# MaTouch_Devkit_AC_Dimmer_V1_2.net
KiCad netlist of a schematic drawn in EAGLE
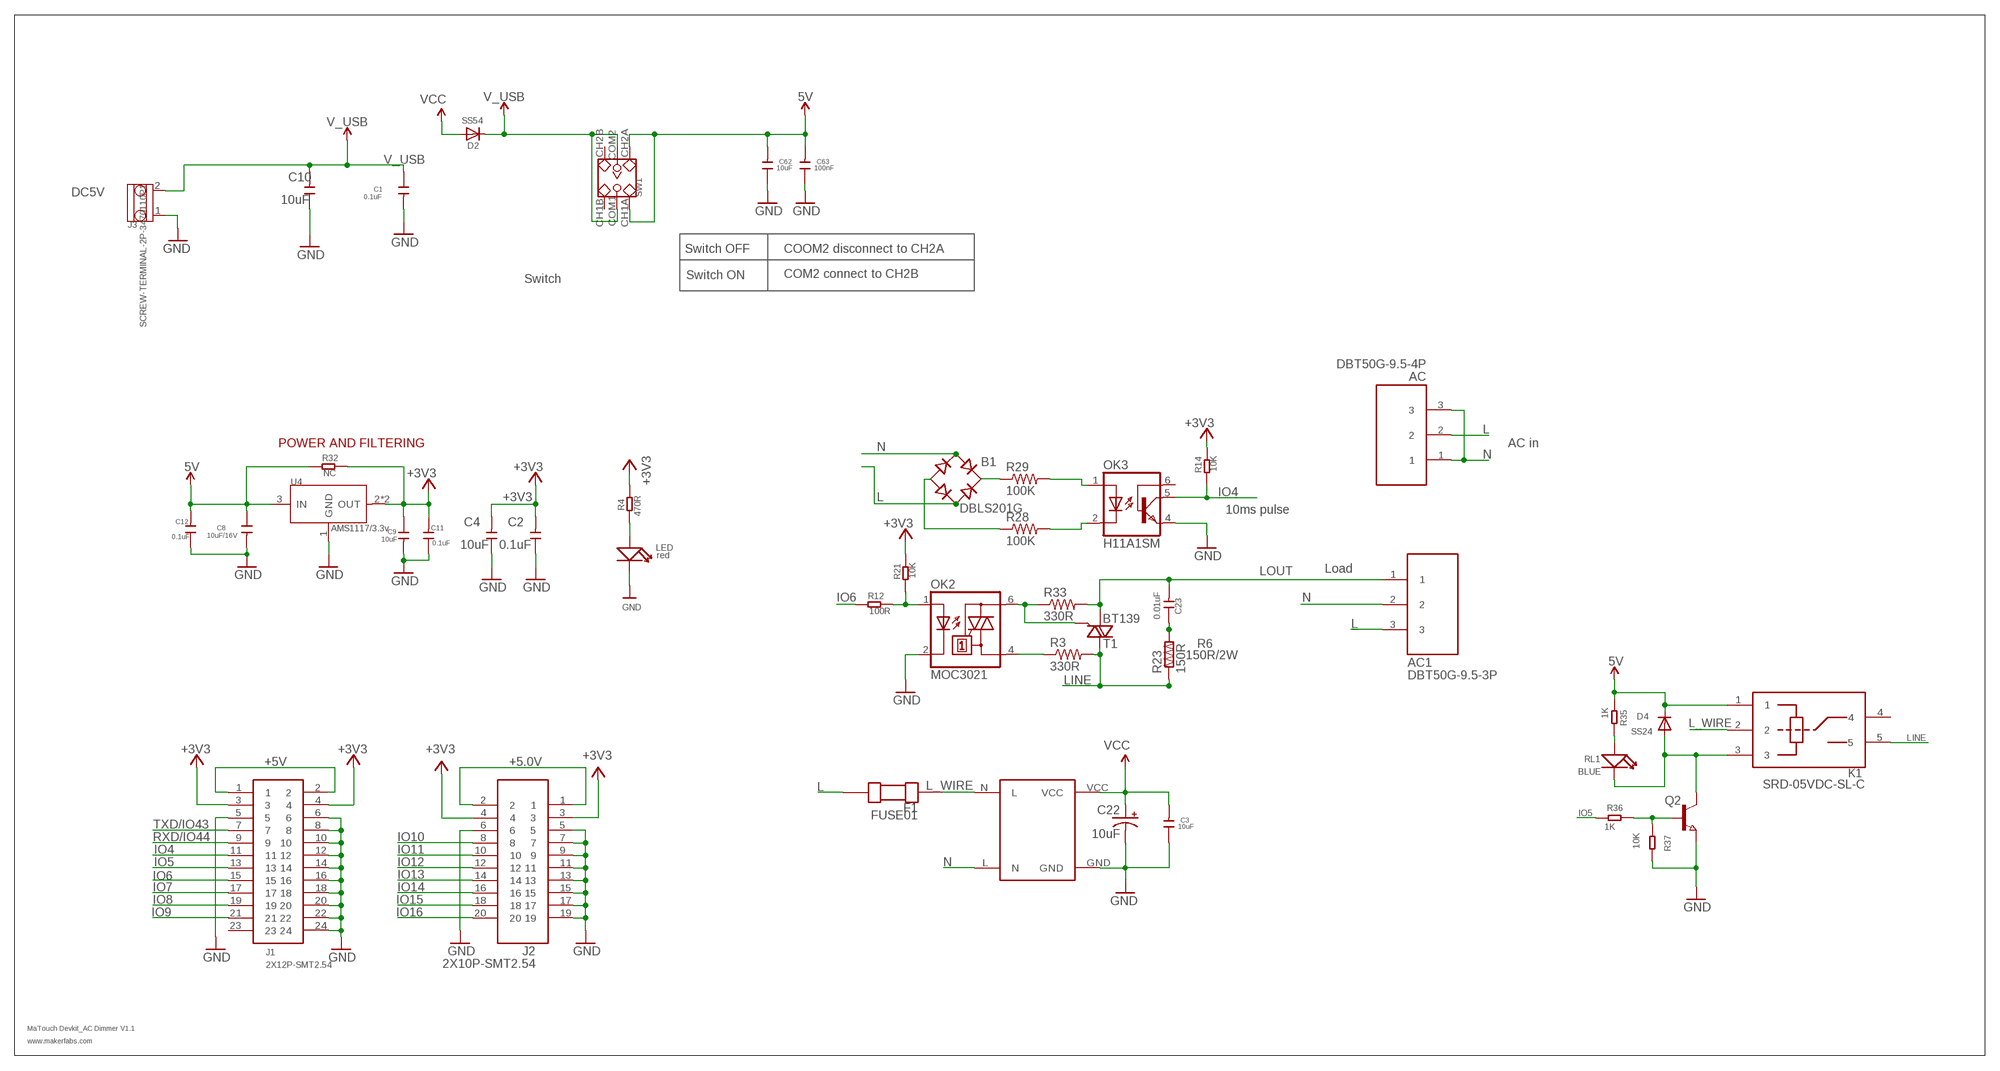
[diagram p0: schematic, sheet 1]

(export (version "E")
  (design (tool "Eeschema 10.0.6"))
  (components
    (comp (ref "AC")
      (value "DBT50G-9.5-4P")
      (footprint "eagle-import:THROUGH-HOLE-9.5")
      (libsource (lib "eagle-import") (part "DBT50G-9.5-3P"))
    )
    (comp (ref "AC1")
      (value "DBT50G-9.5-3P")
      (footprint "eagle-import:THROUGH-HOLE-9.5")
      (libsource (lib "eagle-import") (part "DBT50G-9.5-3P"))
    )
    (comp (ref "B1")
      (value "DBLS201G")
      (footprint "eagle-import:DBS")
      (libsource (lib "eagle-import") (part "DB?GLS201"))
    )
    (comp (ref "C1")
      (value "0.1uF")
      (footprint "eagle-import:0603")
      (libsource (lib "eagle-import") (part "C-0603"))
    )
    (comp (ref "C2")
      (value "0.1uF")
      (footprint "eagle-import:0603")
      (libsource (lib "eagle-import") (part "C-0603"))
    )
    (comp (ref "C3")
      (value "10uF")
      (footprint "eagle-import:0603")
      (libsource (lib "eagle-import") (part "C-0603"))
    )
    (comp (ref "C4")
      (value "10uF")
      (footprint "eagle-import:0603")
      (libsource (lib "eagle-import") (part "C-0603"))
    )
    (comp (ref "C8")
      (value "10uF/16V")
      (footprint "eagle-import:0603")
      (libsource (lib "eagle-import") (part "C-0603"))
    )
    (comp (ref "C9")
      (value "10uF")
      (footprint "eagle-import:0603")
      (libsource (lib "eagle-import") (part "C-0603"))
    )
    (comp (ref "C10")
      (value "10uF")
      (footprint "eagle-import:0603")
      (libsource (lib "eagle-import") (part "C-0603"))
    )
    (comp (ref "C11")
      (value "0.1uF")
      (footprint "eagle-import:0603")
      (libsource (lib "eagle-import") (part "C-0603"))
    )
    (comp (ref "C12")
      (value "0.1uF")
      (footprint "eagle-import:0603")
      (libsource (lib "eagle-import") (part "C-0603"))
    )
    (comp (ref "C22")
      (value "10uF")
      (footprint "eagle-import:EIA3528-KIT")
      (libsource (lib "eagle-import") (part "CAP_POL3528-KIT"))
    )
    (comp (ref "C23")
      (value "0.01uF")
      (footprint "eagle-import:DISCRETE_C0512_10.18")
      (libsource (lib "eagle-import") (part "DISCRETE_C-0512"))
    )
    (comp (ref "C62")
      (value "10uF")
      (footprint "eagle-import:0603")
      (libsource (lib "eagle-import") (part "C-0603"))
    )
    (comp (ref "C63")
      (value "100nF")
      (footprint "eagle-import:0603")
      (libsource (lib "eagle-import") (part "C-0603"))
    )
    (comp (ref "D2")
      (value "SS54")
      (footprint "eagle-import:SMADIODE")
      (libsource (lib "eagle-import") (part "DIODESMA"))
    )
    (comp (ref "D4")
      (value "SS24")
      (footprint "eagle-import:SMADIODE")
      (libsource (lib "eagle-import") (part "DIODESMA"))
    )
    (comp (ref "F1")
      (value "FUSE01")
      (footprint "eagle-import:FUSE01")
      (libsource (lib "eagle-import") (part "FUSE01"))
    )
    (comp (ref "J1")
      (value "2X12P-SMT2.54")
      (footprint "eagle-import:2X12P-SMT2.54")
      (libsource (lib "eagle-import") (part "2X12P-SMT2.54"))
    )
    (comp (ref "J2")
      (value "2X10P-SMT2.54")
      (footprint "eagle-import:2X10P-SMT2.54")
      (libsource (lib "eagle-import") (part "2X10P-SMT2.54"))
    )
    (comp (ref "J3")
      (value "SCREW-TERMINAL-2P-3470110P1")
      (footprint "eagle-import:2P-5.0")
      (libsource (lib "eagle-import") (part "SCREW-TERMINAL-2P-3470110P1"))
    )
    (comp (ref "K1")
      (value "JQC3FF")
      (footprint "eagle-import:DIP5_JQC3FF")
      (libsource (lib "eagle-import") (part "JQC3FF"))
    )
    (comp (ref "LED")
      (value "red")
      (footprint "eagle-import:DISCRETE_LED-0603")
      (libsource (lib "eagle-import") (part "DISCRETE_LED0603"))
    )
    (comp (ref "OK2")
      (value "MOC3021")
      (footprint "eagle-import:DIL6-SMD")
      (fields (field (name "MF") "FAIRCHILD SEMICONDUCTOR") (field (name "MPN") "MOC3031SM"))
      (libsource (lib "eagle-import") (part "MOC30S31"))
    )
    (comp (ref "OK3")
      (value "H11A1SM")
      (footprint "eagle-import:DIL6-SMD")
      (libsource (lib "eagle-import") (part "H11A?MS1"))
    )
    (comp (ref "Q2")
      (value "NPN-TRANSISTOR_SOT23")
      (footprint "eagle-import:SOT23")
      (libsource (lib "eagle-import") (part "NPN-TRANSISTOR_SOT23"))
    )
    (comp (ref "R3")
      (value "330R")
      (footprint "eagle-import:1206")
      (fields (field (name "K") "45K"))
      (libsource (lib "eagle-import") (part "RESISTOR1206"))
    )
    (comp (ref "R4")
      (value "470R")
      (footprint "eagle-import:R0603")
      (libsource (lib "eagle-import") (part "R-0603"))
    )
    (comp (ref "R6")
      (value "150R/2W")
      (footprint "eagle-import:R-0617")
      (libsource (lib "eagle-import") (part "R-0617"))
    )
    (comp (ref "R12")
      (value "100R")
      (footprint "eagle-import:R0603")
      (libsource (lib "eagle-import") (part "R-0603"))
    )
    (comp (ref "R14")
      (value "10K")
      (footprint "eagle-import:R0603")
      (libsource (lib "eagle-import") (part "R-0603"))
    )
    (comp (ref "R21")
      (value "10K")
      (footprint "eagle-import:R0603")
      (libsource (lib "eagle-import") (part "R-0603"))
    )
    (comp (ref "R23")
      (value "150R")
      (footprint "eagle-import:V234_12")
      (libsource (lib "eagle-import") (part "R-US_V234/12"))
    )
    (comp (ref "R28")
      (value "100K")
      (footprint "eagle-import:1206")
      (fields (field (name "K") "45K"))
      (libsource (lib "eagle-import") (part "RESISTOR1206"))
    )
    (comp (ref "R29")
      (value "100K")
      (footprint "eagle-import:1206")
      (fields (field (name "K") "45K"))
      (libsource (lib "eagle-import") (part "RESISTOR1206"))
    )
    (comp (ref "R32")
      (value "NC")
      (footprint "eagle-import:R0603")
      (libsource (lib "eagle-import") (part "R-0603"))
    )
    (comp (ref "R33")
      (value "330R")
      (footprint "eagle-import:1206")
      (fields (field (name "K") "45K"))
      (libsource (lib "eagle-import") (part "RESISTOR1206"))
    )
    (comp (ref "R35")
      (value "1K")
      (footprint "eagle-import:R0603")
      (libsource (lib "eagle-import") (part "R-0603"))
    )
    (comp (ref "R36")
      (value "1K")
      (footprint "eagle-import:R0603")
      (libsource (lib "eagle-import") (part "R-0603"))
    )
    (comp (ref "R37")
      (value "10K")
      (footprint "eagle-import:R0603")
      (libsource (lib "eagle-import") (part "R-0603"))
    )
    (comp (ref "RL1")
      (value "BLUE")
      (footprint "eagle-import:LED-0603")
      (libsource (lib "eagle-import") (part "LED'0603'"))
    )
    (comp (ref "SW1")
      (value "SWITCH-2CH-6P'90D'")
      (footprint "eagle-import:6P-2CH-2.54-9.0X3.6-90D")
      (libsource (lib "eagle-import") (part "SWITCH-2CH-6P'90D'"))
    )
    (comp (ref "T1")
      (value "BT139")
      (footprint "eagle-import:TO220AB")
      (libsource (lib "eagle-import") (part "BT136"))
    )
    (comp (ref "U4")
      (value "AMS1117/3.3v")
      (footprint "eagle-import:SOT89")
      (libsource (lib "eagle-import") (part "LD1117'SOT89'"))
    )
    (comp (ref "U5")
      (value "AC-DCHLK01")
      (footprint "eagle-import:HLK-PM01")
      (libsource (lib "eagle-import") (part "AC-DCHLK01"))
    )
  )
  (nets
    (net (code "1") (name "+3V3") (class "Default")
      (node (ref "C11") (pin "2") (pinfunction "2_2") (pintype "passive"))
      (node (ref "C2") (pin "2") (pinfunction "2_2") (pintype "passive"))
      (node (ref "C4") (pin "2") (pinfunction "2_2") (pintype "passive"))
      (node (ref "C9") (pin "1") (pinfunction "1_1") (pintype "passive"))
      (node (ref "J1") (pin "3") (pinfunction "3_3") (pintype "bidirectional"))
      (node (ref "J1") (pin "4") (pinfunction "4_4") (pintype "bidirectional"))
      (node (ref "J2") (pin "3") (pinfunction "3_3") (pintype "bidirectional"))
      (node (ref "J2") (pin "4") (pinfunction "4_4") (pintype "bidirectional"))
      (node (ref "R14") (pin "2") (pinfunction "2_2") (pintype "passive"))
      (node (ref "R21") (pin "2") (pinfunction "2_2") (pintype "passive"))
      (node (ref "R32") (pin "2") (pinfunction "2_2") (pintype "passive"))
      (node (ref "R4") (pin "2") (pinfunction "2_2") (pintype "passive"))
      (node (ref "U4") (pin "2") (pinfunction "OUT_2") (pintype "bidirectional"))
      (node (ref "U4") (pin "4") (pinfunction "OUT_4") (pintype "bidirectional"))
    )
    (net (code "2") (name "/+5.0V") (class "Default")
      (node (ref "J2") (pin "1") (pinfunction "1_1") (pintype "bidirectional"))
      (node (ref "J2") (pin "2") (pinfunction "2_2") (pintype "bidirectional"))
    )
    (net (code "3") (name "/+5V") (class "Default")
      (node (ref "J1") (pin "1") (pinfunction "1_1") (pintype "bidirectional"))
      (node (ref "J1") (pin "2") (pinfunction "2_2") (pintype "bidirectional"))
    )
    (net (code "4") (name "/IO4") (class "Default")
      (node (ref "J1") (pin "11") (pinfunction "11_11") (pintype "bidirectional"))
      (node (ref "OK3") (pin "5") (pinfunction "COL_5") (pintype "passive"))
      (node (ref "R14") (pin "1") (pinfunction "1_1") (pintype "passive"))
    )
    (net (code "5") (name "/IO5") (class "Default")
      (node (ref "J1") (pin "13") (pinfunction "13_13") (pintype "bidirectional"))
      (node (ref "R36") (pin "1") (pinfunction "1_1") (pintype "passive"))
    )
    (net (code "6") (name "/IO6") (class "Default")
      (node (ref "J1") (pin "15") (pinfunction "15_15") (pintype "bidirectional"))
      (node (ref "R12") (pin "1") (pinfunction "1_1") (pintype "passive"))
    )
    (net (code "7") (name "/IO7") (class "Default")
      (node (ref "J1") (pin "17") (pinfunction "17_17") (pintype "bidirectional"))
    )
    (net (code "8") (name "/IO8") (class "Default")
      (node (ref "J1") (pin "19") (pinfunction "19_19") (pintype "bidirectional"))
    )
    (net (code "9") (name "/IO9") (class "Default")
      (node (ref "J1") (pin "21") (pinfunction "21_21") (pintype "bidirectional"))
    )
    (net (code "10") (name "/IO10") (class "Default")
      (node (ref "J2") (pin "8") (pinfunction "8_8") (pintype "bidirectional"))
    )
    (net (code "11") (name "/IO11") (class "Default")
      (node (ref "J2") (pin "10") (pinfunction "10_10") (pintype "bidirectional"))
    )
    (net (code "12") (name "/IO12") (class "Default")
      (node (ref "J2") (pin "12") (pinfunction "12_12") (pintype "bidirectional"))
    )
    (net (code "13") (name "/IO13") (class "Default")
      (node (ref "J2") (pin "14") (pinfunction "14_14") (pintype "bidirectional"))
    )
    (net (code "14") (name "/IO14") (class "Default")
      (node (ref "J2") (pin "16") (pinfunction "16_16") (pintype "bidirectional"))
    )
    (net (code "15") (name "/IO15") (class "Default")
      (node (ref "J2") (pin "18") (pinfunction "18_18") (pintype "bidirectional"))
    )
    (net (code "16") (name "/IO16") (class "Default")
      (node (ref "J2") (pin "20") (pinfunction "20_20") (pintype "bidirectional"))
    )
    (net (code "17") (name "/L") (class "Default")
      (node (ref "AC") (pin "2") (pinfunction "2_2") (pintype "bidirectional"))
      (node (ref "AC1") (pin "3") (pinfunction "3_3") (pintype "bidirectional"))
      (node (ref "B1") (pin "AC2") (pinfunction "AC2_AC2") (pintype "passive"))
      (node (ref "F1") (pin "P$2") (pinfunction "P$2_P$2") (pintype "bidirectional"))
    )
    (net (code "18") (name "/LINE") (class "Default")
      (node (ref "K1") (pin "5") (pinfunction "5_5") (pintype "bidirectional"))
      (node (ref "R23") (pin "1") (pinfunction "1_1") (pintype "passive"))
      (node (ref "R3") (pin "2") (pinfunction "2_2") (pintype "passive"))
      (node (ref "R6") (pin "1") (pinfunction "1_1") (pintype "passive"))
      (node (ref "T1") (pin "2") (pinfunction "A2_2") (pintype "passive"))
    )
    (net (code "19") (name "/LOUT") (class "Default")
      (node (ref "AC1") (pin "1") (pinfunction "1_1") (pintype "bidirectional"))
      (node (ref "C23") (pin "P$2") (pinfunction "2_P$2") (pintype "passive"))
      (node (ref "R33") (pin "2") (pinfunction "2_2") (pintype "passive"))
      (node (ref "T1") (pin "1") (pinfunction "A1_1") (pintype "passive"))
    )
    (net (code "20") (name "/L_WIRE") (class "Default")
      (node (ref "F1") (pin "P$1") (pinfunction "P$1_P$1") (pintype "bidirectional"))
      (node (ref "K1") (pin "2") (pinfunction "2_2") (pintype "bidirectional"))
      (node (ref "U5") (pin "N") (pinfunction "L_N") (pintype "bidirectional"))
    )
    (net (code "21") (name "/N") (class "Default")
      (node (ref "AC") (pin "1") (pinfunction "1_1") (pintype "bidirectional"))
      (node (ref "AC") (pin "3") (pinfunction "3_3") (pintype "bidirectional"))
      (node (ref "AC1") (pin "2") (pinfunction "2_2") (pintype "bidirectional"))
      (node (ref "B1") (pin "AC1") (pinfunction "AC1_AC1") (pintype "passive"))
      (node (ref "U5") (pin "L") (pinfunction "N_L") (pintype "bidirectional"))
    )
    (net (code "22") (name "/RXD{slash}IO44") (class "Default")
      (node (ref "J1") (pin "9") (pinfunction "9_9") (pintype "bidirectional"))
    )
    (net (code "23") (name "/TXD{slash}IO43") (class "Default")
      (node (ref "J1") (pin "7") (pinfunction "7_7") (pintype "bidirectional"))
    )
    (net (code "24") (name "5V") (class "Default")
      (node (ref "C12") (pin "2") (pinfunction "2_2") (pintype "passive"))
      (node (ref "C62") (pin "2") (pinfunction "2_2") (pintype "passive"))
      (node (ref "C63") (pin "2") (pinfunction "2_2") (pintype "passive"))
      (node (ref "C8") (pin "1") (pinfunction "1_1") (pintype "passive"))
      (node (ref "D4") (pin "C") (pinfunction "C_C") (pintype "passive"))
      (node (ref "K1") (pin "1") (pinfunction "1_1") (pintype "bidirectional"))
      (node (ref "R32") (pin "1") (pinfunction "1_1") (pintype "passive"))
      (node (ref "R35") (pin "1") (pinfunction "1_1") (pintype "passive"))
      (node (ref "SW1") (pin "CH1A") (pinfunction "CH1A_CH1A") (pintype "bidirectional"))
      (node (ref "SW1") (pin "CH2A") (pinfunction "CH2A_CH2A") (pintype "bidirectional"))
      (node (ref "U4") (pin "3") (pinfunction "IN_3") (pintype "bidirectional"))
    )
    (net (code "25") (name "GND") (class "Default")
      (node (ref "C1") (pin "2") (pinfunction "2_2") (pintype "passive"))
      (node (ref "C10") (pin "1") (pinfunction "1_1") (pintype "passive"))
      (node (ref "C11") (pin "1") (pinfunction "1_1") (pintype "passive"))
      (node (ref "C12") (pin "1") (pinfunction "1_1") (pintype "passive"))
      (node (ref "C2") (pin "1") (pinfunction "1_1") (pintype "passive"))
      (node (ref "C22") (pin "C") (pinfunction "-_C") (pintype "passive"))
      (node (ref "C3") (pin "1") (pinfunction "1_1") (pintype "passive"))
      (node (ref "C4") (pin "1") (pinfunction "1_1") (pintype "passive"))
      (node (ref "C62") (pin "1") (pinfunction "1_1") (pintype "passive"))
      (node (ref "C63") (pin "1") (pinfunction "1_1") (pintype "passive"))
      (node (ref "C8") (pin "2") (pinfunction "2_2") (pintype "passive"))
      (node (ref "C9") (pin "2") (pinfunction "2_2") (pintype "passive"))
      (node (ref "J1") (pin "10") (pinfunction "10_10") (pintype "bidirectional"))
      (node (ref "J1") (pin "12") (pinfunction "12_12") (pintype "bidirectional"))
      (node (ref "J1") (pin "14") (pinfunction "14_14") (pintype "bidirectional"))
      (node (ref "J1") (pin "16") (pinfunction "16_16") (pintype "bidirectional"))
      (node (ref "J1") (pin "18") (pinfunction "18_18") (pintype "bidirectional"))
      (node (ref "J1") (pin "20") (pinfunction "20_20") (pintype "bidirectional"))
      (node (ref "J1") (pin "22") (pinfunction "22_22") (pintype "bidirectional"))
      (node (ref "J1") (pin "24") (pinfunction "24_24") (pintype "bidirectional"))
      (node (ref "J1") (pin "5") (pinfunction "5_5") (pintype "bidirectional"))
      (node (ref "J1") (pin "6") (pinfunction "6_6") (pintype "bidirectional"))
      (node (ref "J1") (pin "8") (pinfunction "8_8") (pintype "bidirectional"))
      (node (ref "J2") (pin "11") (pinfunction "11_11") (pintype "bidirectional"))
      (node (ref "J2") (pin "13") (pinfunction "13_13") (pintype "bidirectional"))
      (node (ref "J2") (pin "15") (pinfunction "15_15") (pintype "bidirectional"))
      (node (ref "J2") (pin "17") (pinfunction "17_17") (pintype "bidirectional"))
      (node (ref "J2") (pin "19") (pinfunction "19_19") (pintype "bidirectional"))
      (node (ref "J2") (pin "5") (pinfunction "5_5") (pintype "bidirectional"))
      (node (ref "J2") (pin "6") (pinfunction "6_6") (pintype "bidirectional"))
      (node (ref "J2") (pin "7") (pinfunction "7_7") (pintype "bidirectional"))
      (node (ref "J2") (pin "9") (pinfunction "9_9") (pintype "bidirectional"))
      (node (ref "J3") (pin "1") (pinfunction "1_1") (pintype "bidirectional"))
      (node (ref "LED") (pin "-") (pinfunction "-_-") (pintype "passive"))
      (node (ref "OK2") (pin "2") (pinfunction "C_2") (pintype "passive"))
      (node (ref "OK3") (pin "4") (pinfunction "EMI_4") (pintype "passive"))
      (node (ref "Q2") (pin "2") (pinfunction "E_2") (pintype "passive"))
      (node (ref "R37") (pin "2") (pinfunction "2_2") (pintype "passive"))
      (node (ref "U4") (pin "1") (pinfunction "GND_1") (pintype "bidirectional"))
      (node (ref "U5") (pin "GND") (pinfunction "GND_GND") (pintype "bidirectional"))
    )
    (net (code "26") (name "Net-(B1-Pad+)") (class "Default")
      (node (ref "B1") (pin "+") (pinfunction "+_+") (pintype "passive"))
      (node (ref "R29") (pin "1") (pinfunction "1_1") (pintype "passive"))
    )
    (net (code "27") (name "Net-(B1-Pad-)") (class "Default")
      (node (ref "B1") (pin "-") (pinfunction "-_-") (pintype "passive"))
      (node (ref "R28") (pin "1") (pinfunction "1_1") (pintype "passive"))
    )
    (net (code "28") (name "Net-(C23-1)") (class "Default")
      (node (ref "C23") (pin "P$1") (pinfunction "1_P$1") (pintype "passive"))
      (node (ref "R23") (pin "2") (pinfunction "2_2") (pintype "passive"))
      (node (ref "R6") (pin "2") (pinfunction "2_2") (pintype "passive"))
    )
    (net (code "29") (name "Net-(LED-Pad+)") (class "Default")
      (node (ref "LED") (pin "+") (pinfunction "+_+") (pintype "passive"))
      (node (ref "R4") (pin "1") (pinfunction "1_1") (pintype "passive"))
    )
    (net (code "30") (name "Net-(OK2-A)") (class "Default")
      (node (ref "OK2") (pin "1") (pinfunction "A_1") (pintype "passive"))
      (node (ref "R12") (pin "2") (pinfunction "2_2") (pintype "passive"))
      (node (ref "R21") (pin "1") (pinfunction "1_1") (pintype "passive"))
    )
    (net (code "31") (name "Net-(OK2-A1)") (class "Default")
      (node (ref "OK2") (pin "4") (pinfunction "A1_4") (pintype "passive"))
      (node (ref "R3") (pin "1") (pinfunction "1_1") (pintype "passive"))
    )
    (net (code "32") (name "Net-(OK2-A2)") (class "Default")
      (node (ref "OK2") (pin "6") (pinfunction "A2_6") (pintype "passive"))
      (node (ref "R33") (pin "1") (pinfunction "1_1") (pintype "passive"))
      (node (ref "T1") (pin "3") (pinfunction "G_3") (pintype "passive"))
    )
    (net (code "33") (name "Net-(OK3-A)") (class "Default")
      (node (ref "OK3") (pin "1") (pinfunction "A_1") (pintype "passive"))
      (node (ref "R29") (pin "2") (pinfunction "2_2") (pintype "passive"))
    )
    (net (code "34") (name "Net-(OK3-C)") (class "Default")
      (node (ref "OK3") (pin "2") (pinfunction "C_2") (pintype "passive"))
      (node (ref "R28") (pin "2") (pinfunction "2_2") (pintype "passive"))
    )
    (net (code "35") (name "Net-(Q2-B)") (class "Default")
      (node (ref "Q2") (pin "1") (pinfunction "B_1") (pintype "passive"))
      (node (ref "R36") (pin "2") (pinfunction "2_2") (pintype "passive"))
      (node (ref "R37") (pin "1") (pinfunction "1_1") (pintype "passive"))
    )
    (net (code "36") (name "Net-(Q2-C)") (class "Default")
      (node (ref "D4") (pin "A") (pinfunction "A_A") (pintype "passive"))
      (node (ref "K1") (pin "3") (pinfunction "3_3") (pintype "bidirectional"))
      (node (ref "Q2") (pin "3") (pinfunction "C_3") (pintype "passive"))
      (node (ref "RL1") (pin "-") (pinfunction "-_-") (pintype "passive"))
    )
    (net (code "37") (name "Net-(R35-Pad2)") (class "Default")
      (node (ref "R35") (pin "2") (pinfunction "2_2") (pintype "passive"))
      (node (ref "RL1") (pin "+") (pinfunction "+_+") (pintype "passive"))
    )
    (net (code "38") (name "VCC") (class "Default")
      (node (ref "C22") (pin "A") (pinfunction "+_A") (pintype "passive"))
      (node (ref "C3") (pin "2") (pinfunction "2_2") (pintype "passive"))
      (node (ref "D2") (pin "A") (pinfunction "A_A") (pintype "passive"))
      (node (ref "U5") (pin "VCC") (pinfunction "VCC_VCC") (pintype "bidirectional"))
    )
    (net (code "39") (name "V_USB") (class "Default")
      (node (ref "C1") (pin "1") (pinfunction "1_1") (pintype "passive"))
      (node (ref "C10") (pin "2") (pinfunction "2_2") (pintype "passive"))
      (node (ref "D2") (pin "C") (pinfunction "C_C") (pintype "passive"))
      (node (ref "J3") (pin "2") (pinfunction "2_2") (pintype "bidirectional"))
      (node (ref "SW1") (pin "COM1") (pinfunction "COM1_COM1") (pintype "bidirectional"))
      (node (ref "SW1") (pin "COM2") (pinfunction "COM2_COM2") (pintype "bidirectional"))
    )
    (net (code "40") (name "unconnected-(J1-Pad23)") (class "Default")
      (node (ref "J1") (pin "23") (pinfunction "23_23") (pintype "bidirectional"))
    )
    (net (code "41") (name "unconnected-(K1-Pad4)") (class "Default")
      (node (ref "K1") (pin "4") (pinfunction "4_4") (pintype "bidirectional"))
    )
    (net (code "42") (name "unconnected-(OK3-BAS-Pad6)") (class "Default")
      (node (ref "OK3") (pin "6") (pinfunction "BAS_6") (pintype "passive"))
    )
    (net (code "43") (name "unconnected-(SW1-PadCH1B)") (class "Default")
      (node (ref "SW1") (pin "CH1B") (pinfunction "CH1B_CH1B") (pintype "bidirectional"))
    )
    (net (code "44") (name "unconnected-(SW1-PadCH2B)") (class "Default")
      (node (ref "SW1") (pin "CH2B") (pinfunction "CH2B_CH2B") (pintype "bidirectional"))
    )
  )
)
